# LEDremote.net
KiCad netlist of a schematic drawn in Altium Designer
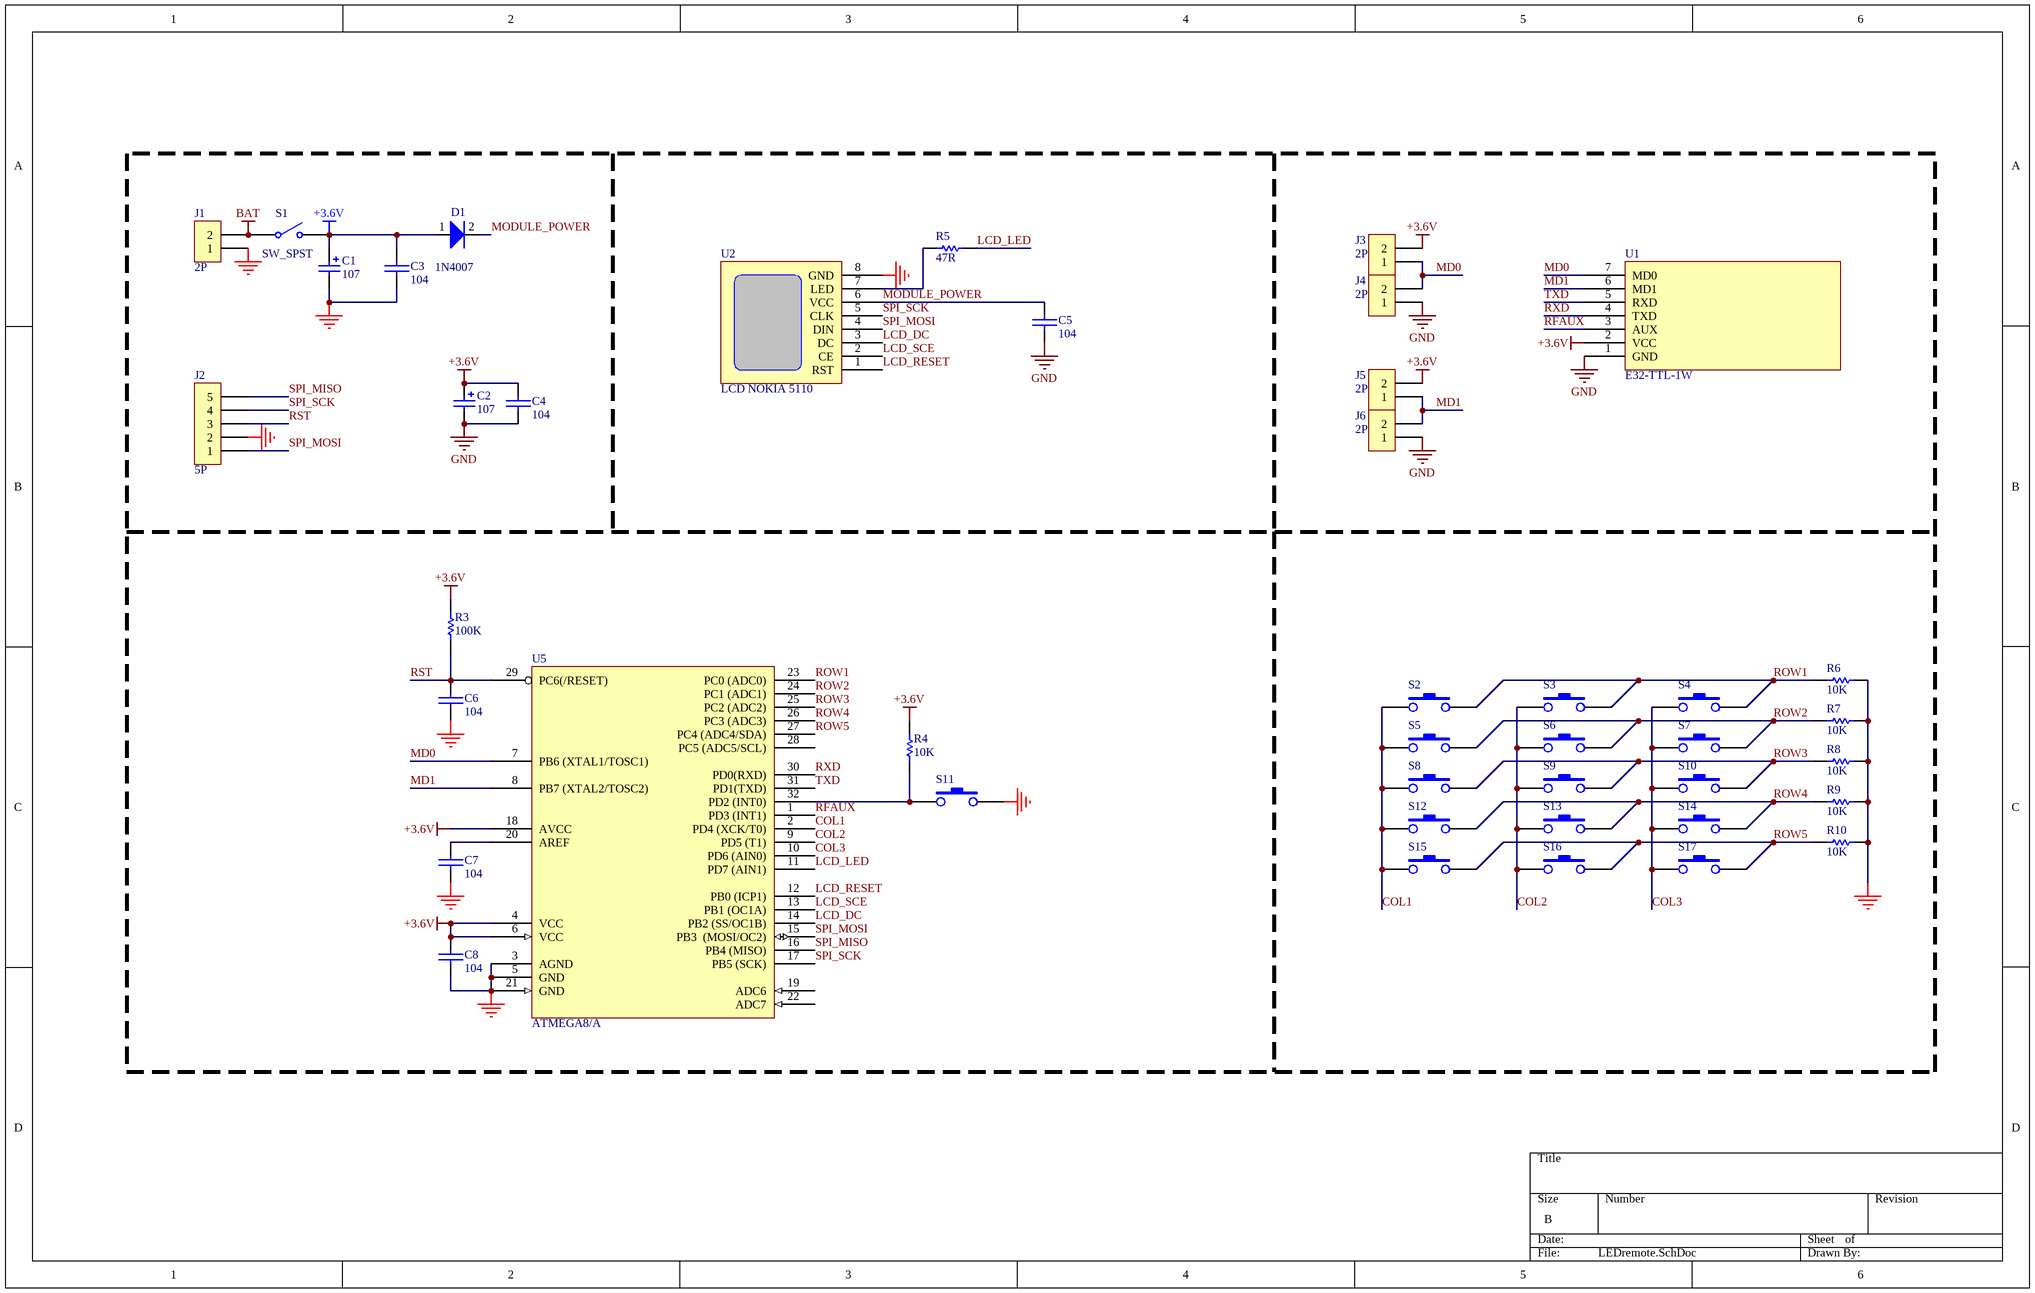
[diagram p0: LEDremote.SchDoc]

(export (version "E")
  (design (tool "Eeschema 10.0.6"))
  (components
    (comp (ref "C1")
      (value "107")
      (footprint "SMC_D/WA")
      (description "Polarized Capacitor (Radial)")
      (fields (field (name "Comment") "Tụ hóa chân dán107") (field (name "PUBLISHER") "*"))
      (libsource (lib "DnsSchLib") (part "Cap Pol1"))
    )
    (comp (ref "C2")
      (value "107")
      (footprint "SMC_E/WA")
      (description "Polarized Capacitor (Radial)")
      (fields (field (name "Comment") "Tụ hóa chân dán107") (field (name "PUBLISHER") "*"))
      (libsource (lib "DnsSchLib") (part "Cap Pol1"))
    )
    (comp (ref "C3")
      (value "104")
      (footprint "0805C")
      (fields (field (name "Comment") "Tụ điện dán 0805104"))
      (libsource (lib "DnsSchLib") (part "CAP"))
    )
    (comp (ref "C4")
      (value "104")
      (footprint "0805C")
      (fields (field (name "Comment") "Tụ điện dán 0805104"))
      (libsource (lib "DnsSchLib") (part "CAP"))
    )
    (comp (ref "C5")
      (value "104")
      (footprint "0805C")
      (fields (field (name "Comment") "Tụ điện dán 0805104"))
      (libsource (lib "DnsSchLib") (part "CAP"))
    )
    (comp (ref "C6")
      (value "104")
      (footprint "0805C")
      (fields (field (name "Comment") "Tụ điện dán 0805104"))
      (libsource (lib "DnsSchLib") (part "CAP"))
    )
    (comp (ref "C7")
      (value "104")
      (footprint "0805C")
      (fields (field (name "Comment") "Tụ điện dán 0805104"))
      (libsource (lib "DnsSchLib") (part "CAP"))
    )
    (comp (ref "C8")
      (value "104")
      (footprint "0805C")
      (fields (field (name "Comment") "Tụ điện dán 0805104"))
      (libsource (lib "DnsSchLib") (part "CAP"))
    )
    (comp (ref "D1")
      (value "Diode chân dán 1A1N4007")
      (footprint "SMC_D/WA")
      (fields (field (name "VALUE2") "1N4007"))
      (libsource (lib "DnsSchLib") (part "DIODE"))
    )
    (comp (ref "J1")
      (value "2P")
      (footprint "HDR1x2")
      (fields (field (name "Comment") "Jump đực loại thẳng, 2.54mm2P"))
      (libsource (lib "DnsSchLib") (part "CON2"))
    )
    (comp (ref "J2")
      (value "5P")
      (footprint "HDR1x5")
      (description "Connector")
      (fields (field (name "Comment") "Jump đực chân thẳng, 2.54mm 5P"))
      (libsource (lib "*") (part "CON5"))
    )
    (comp (ref "J3")
      (value "2P")
      (footprint "XPAD")
      (fields (field (name "Comment") "Jumper2P"))
      (libsource (lib "DnsSchLib") (part "CON2"))
    )
    (comp (ref "J4")
      (value "2P")
      (footprint "XPAD")
      (fields (field (name "Comment") "Jumper2P"))
      (libsource (lib "DnsSchLib") (part "CON2"))
    )
    (comp (ref "J5")
      (value "2P")
      (footprint "XPAD")
      (fields (field (name "Comment") "Jumper2P"))
      (libsource (lib "DnsSchLib") (part "CON2"))
    )
    (comp (ref "J6")
      (value "2P")
      (footprint "XPAD")
      (fields (field (name "Comment") "Jumper2P"))
      (libsource (lib "DnsSchLib") (part "CON2"))
    )
    (comp (ref "R3")
      (value "100K")
      (footprint "0805DD")
      (description "Semiconductor Resistor")
      (fields (field (name "Comment") "Điện trở dán 0805100K") (field (name "PUBLISHER") "*"))
      (libsource (lib "DnsSchLib") (part "Res Semi"))
    )
    (comp (ref "R4")
      (value "10K")
      (footprint "0805DD")
      (description "Semiconductor Resistor")
      (fields (field (name "Comment") "Điện trở dán 080510K") (field (name "PUBLISHER") "*"))
      (libsource (lib "DnsSchLib") (part "Res Semi"))
    )
    (comp (ref "R5")
      (value "47R")
      (footprint "0805DD")
      (description "Semiconductor Resistor")
      (fields (field (name "Comment") "Điện trở dán 080547R") (field (name "PUBLISHER") "*"))
      (libsource (lib "DnsSchLib") (part "Res Semi"))
    )
    (comp (ref "R6")
      (value "10K")
      (footprint "0805DD")
      (description "Semiconductor Resistor")
      (fields (field (name "Comment") "Điện trở dán 080510K") (field (name "PUBLISHER") "*"))
      (libsource (lib "DnsSchLib") (part "Res Semi"))
    )
    (comp (ref "R7")
      (value "10K")
      (footprint "0805DD")
      (description "Semiconductor Resistor")
      (fields (field (name "Comment") "Điện trở dán 080510K") (field (name "PUBLISHER") "*"))
      (libsource (lib "DnsSchLib") (part "Res Semi"))
    )
    (comp (ref "R8")
      (value "10K")
      (footprint "0805DD")
      (description "Semiconductor Resistor")
      (fields (field (name "Comment") "Điện trở dán 080510K") (field (name "PUBLISHER") "*"))
      (libsource (lib "DnsSchLib") (part "Res Semi"))
    )
    (comp (ref "R9")
      (value "10K")
      (footprint "0805DD")
      (description "Semiconductor Resistor")
      (fields (field (name "Comment") "Điện trở dán 080510K") (field (name "PUBLISHER") "*"))
      (libsource (lib "DnsSchLib") (part "Res Semi"))
    )
    (comp (ref "R10")
      (value "10K")
      (footprint "0805DD")
      (description "Semiconductor Resistor")
      (fields (field (name "Comment") "Điện trở dán 080510K") (field (name "PUBLISHER") "*"))
      (libsource (lib "DnsSchLib") (part "Res Semi"))
    )
    (comp (ref "S1")
      (value "SW_SPST")
      (footprint "SPST-2")
      (description "Single-Pole, Single-Throw Switch")
      (fields (field (name "Comment") "Công tắc chân cắm BIT X1") (field (name "PUBLISHER") "Altium Limited"))
      (libsource (lib "Miscellaneous Devices") (part "SW-SPST"))
    )
    (comp (ref "S2")
      (value "Công tắc chip chân cắm, 4 chân6x6x4mm")
      (footprint "CHIP")
      (libsource (lib "DnsSchLib") (part "SW-PB"))
    )
    (comp (ref "S3")
      (value "Công tắc chip chân cắm, 4 chân6x6x4mm")
      (footprint "CHIP")
      (libsource (lib "DnsSchLib") (part "SW-PB"))
    )
    (comp (ref "S4")
      (value "Công tắc chip chân cắm, 4 chân6x6x4mm")
      (footprint "CHIP")
      (libsource (lib "DnsSchLib") (part "SW-PB"))
    )
    (comp (ref "S5")
      (value "Công tắc chip chân cắm, 4 chân6x6x4mm")
      (footprint "CHIP")
      (libsource (lib "DnsSchLib") (part "SW-PB"))
    )
    (comp (ref "S6")
      (value "Công tắc chip chân cắm, 4 chân6x6x4mm")
      (footprint "CHIP")
      (libsource (lib "DnsSchLib") (part "SW-PB"))
    )
    (comp (ref "S7")
      (value "Công tắc chip chân cắm, 4 chân6x6x4mm")
      (footprint "CHIP")
      (libsource (lib "DnsSchLib") (part "SW-PB"))
    )
    (comp (ref "S8")
      (value "Công tắc chip chân cắm, 4 chân6x6x4mm")
      (footprint "CHIP")
      (libsource (lib "DnsSchLib") (part "SW-PB"))
    )
    (comp (ref "S9")
      (value "Công tắc chip chân cắm, 4 chân6x6x4mm")
      (footprint "CHIP")
      (libsource (lib "DnsSchLib") (part "SW-PB"))
    )
    (comp (ref "S10")
      (value "Công tắc chip chân cắm, 4 chân6x6x4mm")
      (footprint "CHIP")
      (libsource (lib "DnsSchLib") (part "SW-PB"))
    )
    (comp (ref "S11")
      (value "Công tắc chip chân cắm, 4 chân6x6x4mm")
      (footprint "CHIP")
      (libsource (lib "DnsSchLib") (part "SW-PB"))
    )
    (comp (ref "S12")
      (value "Công tắc chip chân cắm, 4 chân6x6x4mm")
      (footprint "CHIP")
      (libsource (lib "DnsSchLib") (part "SW-PB"))
    )
    (comp (ref "S13")
      (value "Công tắc chip chân cắm, 4 chân6x6x4mm")
      (footprint "CHIP")
      (libsource (lib "DnsSchLib") (part "SW-PB"))
    )
    (comp (ref "S14")
      (value "Công tắc chip chân cắm, 4 chân6x6x4mm")
      (footprint "CHIP")
      (libsource (lib "DnsSchLib") (part "SW-PB"))
    )
    (comp (ref "S15")
      (value "Công tắc chip chân cắm, 4 chân6x6x4mm")
      (footprint "CHIP")
      (libsource (lib "DnsSchLib") (part "SW-PB"))
    )
    (comp (ref "S16")
      (value "Công tắc chip chân cắm, 4 chân6x6x4mm")
      (footprint "CHIP")
      (libsource (lib "DnsSchLib") (part "SW-PB"))
    )
    (comp (ref "S17")
      (value "Công tắc chip chân cắm, 4 chân6x6x4mm")
      (footprint "CHIP")
      (libsource (lib "DnsSchLib") (part "SW-PB"))
    )
    (comp (ref "U1")
      (value "E32-TTL-1W")
      (footprint "RF_AS32")
      (description "AS32-TTL-1W")
      (fields (field (name "Comment") "Module thu phát không dây RFE32-TTL-1W"))
      (libsource (lib "DnsSchLib") (part "AS32-TTL-1W"))
    )
    (comp (ref "U2")
      (value "LCD NOKIA 5110")
      (footprint "NOKIA5110T")
      (libsource (lib "DnsSchLib") (part "LCD NOKIA 5110"))
    )
    (comp (ref "U5")
      (value "ATMEGA8/A")
      (footprint "ATMEGA8")
      (description "TQFP package")
      (fields (field (name "Comment") "Vi điều khiển ATMEL chân dánATMEGA8/A"))
      (libsource (lib "DnsSchLib") (part "ATMEGA8-A"))
    )
  )
  (nets
    (net (code "1") (name "+3.6V") (class "Default")
      (node (ref "C1") (pin "1") (pinfunction "1_1") (pintype "passive"))
      (node (ref "C2") (pin "1") (pinfunction "1_1") (pintype "passive"))
      (node (ref "C3") (pin "1") (pinfunction "1_1") (pintype "passive"))
      (node (ref "C4") (pin "2") (pinfunction "2_2") (pintype "passive"))
      (node (ref "C8") (pin "1") (pinfunction "1_1") (pintype "passive"))
      (node (ref "D1") (pin "1") (pinfunction "A_1") (pintype "passive"))
      (node (ref "J3") (pin "2") (pinfunction "2_2") (pintype "passive"))
      (node (ref "J5") (pin "2") (pinfunction "2_2") (pintype "passive"))
      (node (ref "R3") (pin "2") (pinfunction "2_2") (pintype "passive"))
      (node (ref "R4") (pin "2") (pinfunction "2_2") (pintype "passive"))
      (node (ref "S1") (pin "2") (pinfunction "NO_2") (pintype "passive"))
      (node (ref "U1") (pin "2") (pinfunction "VCC_2") (pintype "passive"))
      (node (ref "U5") (pin "18") (pinfunction "AVCC_18") (pintype "passive"))
      (node (ref "U5") (pin "4") (pinfunction "VCC_4") (pintype "passive"))
      (node (ref "U5") (pin "6") (pinfunction "VCC_6") (pintype "input"))
    )
    (net (code "2") (name "/COL1") (class "Default")
      (node (ref "S12") (pin "1") (pinfunction "1_1") (pintype "passive"))
      (node (ref "S15") (pin "1") (pinfunction "1_1") (pintype "passive"))
      (node (ref "S2") (pin "1") (pinfunction "1_1") (pintype "passive"))
      (node (ref "S5") (pin "1") (pinfunction "1_1") (pintype "passive"))
      (node (ref "S8") (pin "1") (pinfunction "1_1") (pintype "passive"))
      (node (ref "U5") (pin "2") (pinfunction "PD4_(XCK/T0)_2") (pintype "passive"))
    )
    (net (code "3") (name "/COL2") (class "Default")
      (node (ref "S13") (pin "1") (pinfunction "1_1") (pintype "passive"))
      (node (ref "S16") (pin "1") (pinfunction "1_1") (pintype "passive"))
      (node (ref "S3") (pin "1") (pinfunction "1_1") (pintype "passive"))
      (node (ref "S6") (pin "1") (pinfunction "1_1") (pintype "passive"))
      (node (ref "S9") (pin "1") (pinfunction "1_1") (pintype "passive"))
      (node (ref "U5") (pin "9") (pinfunction "PD5_(T1)_9") (pintype "passive"))
    )
    (net (code "4") (name "/COL3") (class "Default")
      (node (ref "S10") (pin "1") (pinfunction "1_1") (pintype "passive"))
      (node (ref "S14") (pin "1") (pinfunction "1_1") (pintype "passive"))
      (node (ref "S17") (pin "1") (pinfunction "1_1") (pintype "passive"))
      (node (ref "S4") (pin "1") (pinfunction "1_1") (pintype "passive"))
      (node (ref "S7") (pin "1") (pinfunction "1_1") (pintype "passive"))
      (node (ref "U5") (pin "10") (pinfunction "PD6_(AIN0)_10") (pintype "passive"))
    )
    (net (code "5") (name "/LCD_DC") (class "Default")
      (node (ref "U2") (pin "3") (pinfunction "DC_3") (pintype "passive"))
      (node (ref "U5") (pin "14") (pinfunction "PB2_(SS/OC1B)_14") (pintype "passive"))
    )
    (net (code "6") (name "/LCD_LED") (class "Default")
      (node (ref "R5") (pin "2") (pinfunction "2_2") (pintype "passive"))
      (node (ref "U5") (pin "11") (pinfunction "PD7_(AIN1)_11") (pintype "passive"))
    )
    (net (code "7") (name "/LCD_RESET") (class "Default")
      (node (ref "U2") (pin "1") (pinfunction "RST_1") (pintype "passive"))
      (node (ref "U5") (pin "12") (pinfunction "PB0_(ICP1)_12") (pintype "passive"))
    )
    (net (code "8") (name "/LCD_SCE") (class "Default")
      (node (ref "U2") (pin "2") (pinfunction "CE_2") (pintype "passive"))
      (node (ref "U5") (pin "13") (pinfunction "PB1_(OC1A)_13") (pintype "passive"))
    )
    (net (code "9") (name "/MD0") (class "Default")
      (node (ref "J3") (pin "1") (pinfunction "1_1") (pintype "passive"))
      (node (ref "J4") (pin "2") (pinfunction "2_2") (pintype "passive"))
      (node (ref "U1") (pin "7") (pinfunction "MD0_7") (pintype "passive"))
      (node (ref "U5") (pin "7") (pinfunction "PB6_(XTAL1/TOSC1)_7") (pintype "passive"))
    )
    (net (code "10") (name "/MD1") (class "Default")
      (node (ref "J5") (pin "1") (pinfunction "1_1") (pintype "passive"))
      (node (ref "J6") (pin "2") (pinfunction "2_2") (pintype "passive"))
      (node (ref "U1") (pin "6") (pinfunction "MD1_6") (pintype "passive"))
      (node (ref "U5") (pin "8") (pinfunction "PB7_(XTAL2/TOSC2)_8") (pintype "passive"))
    )
    (net (code "11") (name "/MODULE_POWER") (class "Default")
      (node (ref "C5") (pin "1") (pinfunction "1_1") (pintype "passive"))
      (node (ref "D1") (pin "2") (pinfunction "K_2") (pintype "passive"))
      (node (ref "U2") (pin "6") (pinfunction "VCC_6") (pintype "passive"))
    )
    (net (code "12") (name "/RFAUX") (class "Default")
      (node (ref "U1") (pin "3") (pinfunction "AUX_3") (pintype "passive"))
      (node (ref "U5") (pin "1") (pinfunction "PD3_(INT1)_1") (pintype "passive"))
    )
    (net (code "13") (name "/ROW1") (class "Default")
      (node (ref "R6") (pin "1") (pinfunction "1_1") (pintype "passive"))
      (node (ref "S2") (pin "2") (pinfunction "2_2") (pintype "passive"))
      (node (ref "S3") (pin "2") (pinfunction "2_2") (pintype "passive"))
      (node (ref "S4") (pin "2") (pinfunction "2_2") (pintype "passive"))
      (node (ref "U5") (pin "23") (pinfunction "PC0_(ADC0)_23") (pintype "passive"))
    )
    (net (code "14") (name "/ROW2") (class "Default")
      (node (ref "R7") (pin "1") (pinfunction "1_1") (pintype "passive"))
      (node (ref "S5") (pin "2") (pinfunction "2_2") (pintype "passive"))
      (node (ref "S6") (pin "2") (pinfunction "2_2") (pintype "passive"))
      (node (ref "S7") (pin "2") (pinfunction "2_2") (pintype "passive"))
      (node (ref "U5") (pin "24") (pinfunction "PC1_(ADC1)_24") (pintype "passive"))
    )
    (net (code "15") (name "/ROW3") (class "Default")
      (node (ref "R8") (pin "1") (pinfunction "1_1") (pintype "passive"))
      (node (ref "S10") (pin "2") (pinfunction "2_2") (pintype "passive"))
      (node (ref "S8") (pin "2") (pinfunction "2_2") (pintype "passive"))
      (node (ref "S9") (pin "2") (pinfunction "2_2") (pintype "passive"))
      (node (ref "U5") (pin "25") (pinfunction "PC2_(ADC2)_25") (pintype "passive"))
    )
    (net (code "16") (name "/ROW4") (class "Default")
      (node (ref "R9") (pin "1") (pinfunction "1_1") (pintype "passive"))
      (node (ref "S12") (pin "2") (pinfunction "2_2") (pintype "passive"))
      (node (ref "S13") (pin "2") (pinfunction "2_2") (pintype "passive"))
      (node (ref "S14") (pin "2") (pinfunction "2_2") (pintype "passive"))
      (node (ref "U5") (pin "26") (pinfunction "PC3_(ADC3)_26") (pintype "passive"))
    )
    (net (code "17") (name "/ROW5") (class "Default")
      (node (ref "R10") (pin "1") (pinfunction "1_1") (pintype "passive"))
      (node (ref "S15") (pin "2") (pinfunction "2_2") (pintype "passive"))
      (node (ref "S16") (pin "2") (pinfunction "2_2") (pintype "passive"))
      (node (ref "S17") (pin "2") (pinfunction "2_2") (pintype "passive"))
      (node (ref "U5") (pin "27") (pinfunction "PC4_(ADC4/SDA)_27") (pintype "passive"))
    )
    (net (code "18") (name "/RST") (class "Default")
      (node (ref "C6") (pin "1") (pinfunction "1_1") (pintype "passive"))
      (node (ref "J2") (pin "3") (pinfunction "3_3") (pintype "passive"))
      (node (ref "R3") (pin "1") (pinfunction "1_1") (pintype "passive"))
      (node (ref "U5") (pin "29") (pinfunction "PC6(/RESET)_29") (pintype "passive"))
    )
    (net (code "19") (name "/RXD") (class "Default")
      (node (ref "U1") (pin "4") (pinfunction "TXD_4") (pintype "passive"))
      (node (ref "U5") (pin "30") (pinfunction "PD0(RXD)_30") (pintype "passive"))
    )
    (net (code "20") (name "/SPI_MISO") (class "Default")
      (node (ref "J2") (pin "5") (pinfunction "5_5") (pintype "passive"))
      (node (ref "U5") (pin "16") (pinfunction "PB4_(MISO)_16") (pintype "passive"))
    )
    (net (code "21") (name "/SPI_MOSI") (class "Default")
      (node (ref "J2") (pin "1") (pinfunction "1_1") (pintype "passive"))
      (node (ref "U2") (pin "4") (pinfunction "DIN_4") (pintype "passive"))
      (node (ref "U5") (pin "15") (pinfunction "PB3__(MOSI/OC2)_15") (pintype "bidirectional"))
    )
    (net (code "22") (name "/SPI_SCK") (class "Default")
      (node (ref "J2") (pin "4") (pinfunction "4_4") (pintype "passive"))
      (node (ref "U2") (pin "5") (pinfunction "CLK_5") (pintype "passive"))
      (node (ref "U5") (pin "17") (pinfunction "PB5_(SCK)_17") (pintype "passive"))
    )
    (net (code "23") (name "/TXD") (class "Default")
      (node (ref "U1") (pin "5") (pinfunction "RXD_5") (pintype "passive"))
      (node (ref "U5") (pin "31") (pinfunction "PD1(TXD)_31") (pintype "passive"))
    )
    (net (code "24") (name "BAT") (class "Default")
      (node (ref "J1") (pin "2") (pinfunction "2_2") (pintype "passive"))
      (node (ref "S1") (pin "1") (pinfunction "COMMON_1") (pintype "passive"))
    )
    (net (code "25") (name "GND") (class "Default")
      (node (ref "C1") (pin "2") (pinfunction "2_2") (pintype "passive"))
      (node (ref "C2") (pin "2") (pinfunction "2_2") (pintype "passive"))
      (node (ref "C3") (pin "2") (pinfunction "2_2") (pintype "passive"))
      (node (ref "C4") (pin "1") (pinfunction "1_1") (pintype "passive"))
      (node (ref "C5") (pin "2") (pinfunction "2_2") (pintype "passive"))
      (node (ref "C6") (pin "2") (pinfunction "2_2") (pintype "passive"))
      (node (ref "C7") (pin "2") (pinfunction "2_2") (pintype "passive"))
      (node (ref "C8") (pin "2") (pinfunction "2_2") (pintype "passive"))
      (node (ref "J1") (pin "1") (pinfunction "1_1") (pintype "passive"))
      (node (ref "J2") (pin "2") (pinfunction "2_2") (pintype "passive"))
      (node (ref "J4") (pin "1") (pinfunction "1_1") (pintype "passive"))
      (node (ref "J6") (pin "1") (pinfunction "1_1") (pintype "passive"))
      (node (ref "R10") (pin "2") (pinfunction "2_2") (pintype "passive"))
      (node (ref "R6") (pin "2") (pinfunction "2_2") (pintype "passive"))
      (node (ref "R7") (pin "2") (pinfunction "2_2") (pintype "passive"))
      (node (ref "R8") (pin "2") (pinfunction "2_2") (pintype "passive"))
      (node (ref "R9") (pin "2") (pinfunction "2_2") (pintype "passive"))
      (node (ref "S11") (pin "2") (pinfunction "2_2") (pintype "passive"))
      (node (ref "U1") (pin "1") (pinfunction "GND_1") (pintype "passive"))
      (node (ref "U2") (pin "8") (pinfunction "GND_8") (pintype "passive"))
      (node (ref "U5") (pin "21") (pinfunction "GND_21") (pintype "input"))
      (node (ref "U5") (pin "3") (pinfunction "AGND_3") (pintype "passive"))
      (node (ref "U5") (pin "5") (pinfunction "GND_5") (pintype "passive"))
    )
    (net (code "26") (name "Net-(U2-LED)") (class "Default")
      (node (ref "R5") (pin "1") (pinfunction "1_1") (pintype "passive"))
      (node (ref "U2") (pin "7") (pinfunction "LED_7") (pintype "passive"))
    )
    (net (code "27") (name "Net-(U5-AREF)") (class "Default")
      (node (ref "C7") (pin "1") (pinfunction "1_1") (pintype "passive"))
      (node (ref "U5") (pin "20") (pinfunction "AREF_20") (pintype "passive"))
    )
    (net (code "28") (name "Net-(U5-PD2_(INT0))") (class "Default")
      (node (ref "R4") (pin "1") (pinfunction "1_1") (pintype "passive"))
      (node (ref "S11") (pin "1") (pinfunction "1_1") (pintype "passive"))
      (node (ref "U5") (pin "32") (pinfunction "PD2_(INT0)_32") (pintype "passive"))
    )
    (net (code "29") (name "unconnected-(U5-ADC6-Pad19)") (class "Default")
      (node (ref "U5") (pin "19") (pinfunction "ADC6_19") (pintype "input"))
    )
    (net (code "30") (name "unconnected-(U5-ADC7-Pad22)") (class "Default")
      (node (ref "U5") (pin "22") (pinfunction "ADC7_22") (pintype "input"))
    )
    (net (code "31") (name "unconnected-(U5-PC5_(ADC5{slash}SCL)-Pad28)") (class "Default")
      (node (ref "U5") (pin "28") (pinfunction "PC5_(ADC5/SCL)_28") (pintype "passive"))
    )
  )
)
